# Power.net
KiCad netlist of a schematic drawn in Altium Designer
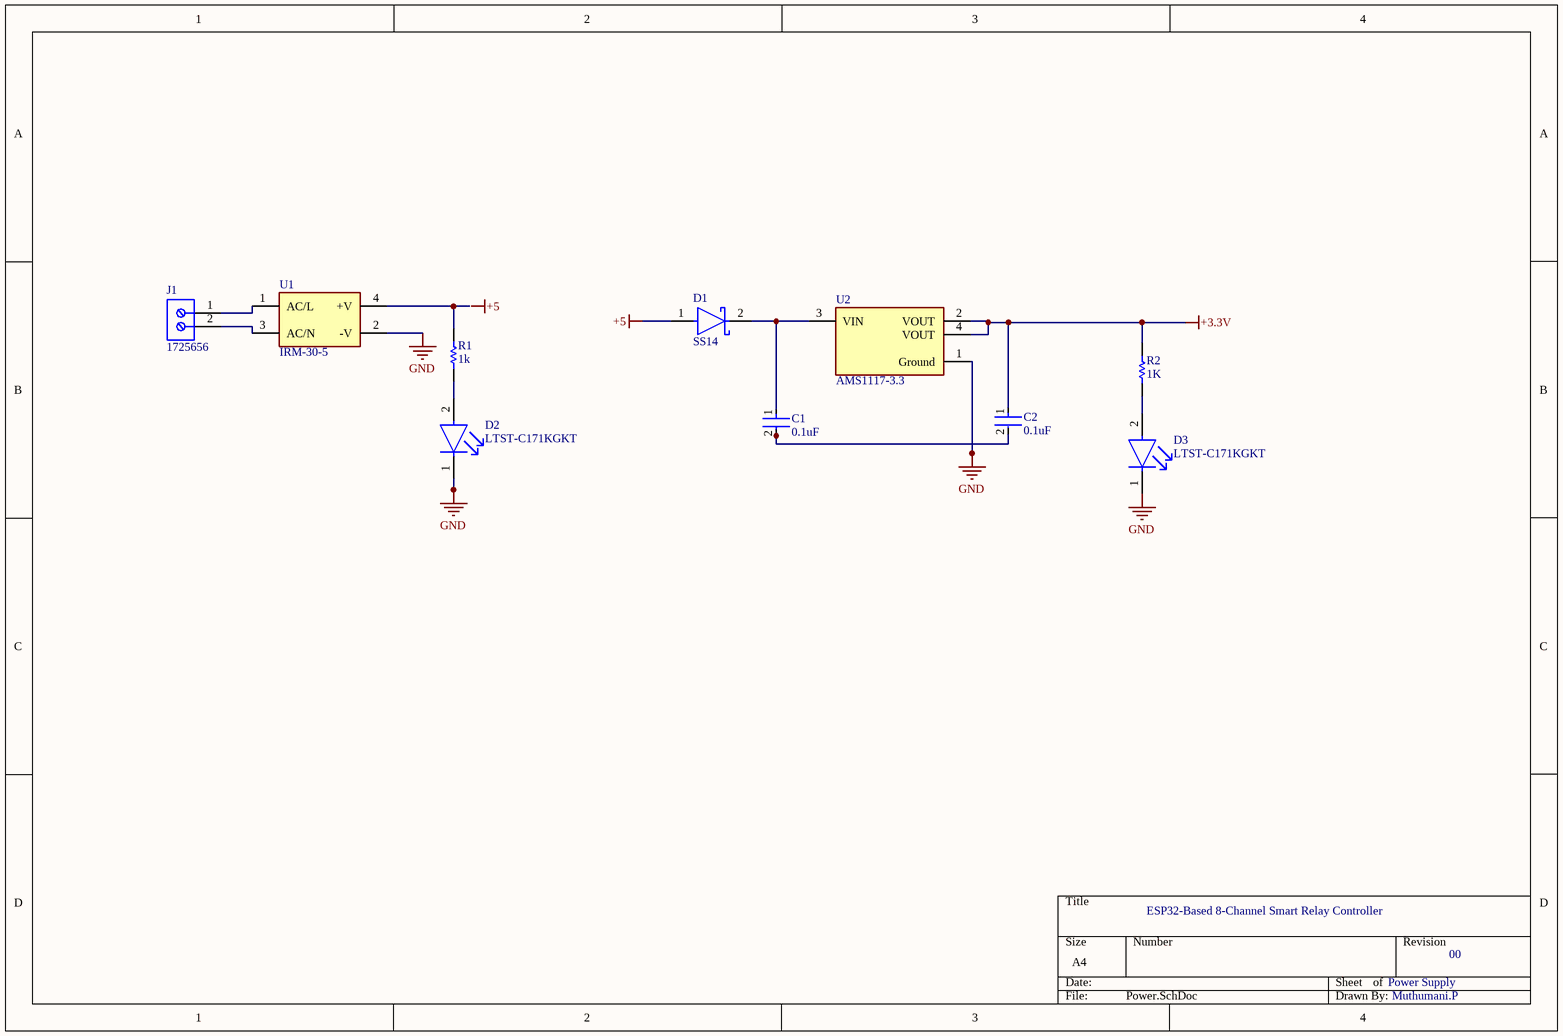
[diagram p0: Power.SchDoc]

(export (version "E")
  (design (tool "Eeschema 10.0.6"))
  (components
    (comp (ref "C1")
      (value "0.1uF")
      (footprint "FP-1206-L_3_2_0_2-W_1_6_0-MFG")
      (description "General Purpose Ceramic Capacitor, 1206, 2.2uF, 20%, X7R, 15%, 100V")
      (fields (field (name "TOLERANCE") "20%"))
      (libsource (lib "Altium Content Vault") (part "b4654b650e69147ec39a6b967a45e02"))
    )
    (comp (ref "C2")
      (value "0.1uF")
      (footprint "FP-1206-L_3_2_0_2-W_1_6_0-MFG")
      (description "General Purpose Ceramic Capacitor, 1206, 2.2uF, 20%, X7R, 15%, 100V")
      (fields (field (name "TOLERANCE") "20%"))
      (libsource (lib "Altium Content Vault") (part "b4654b650e69147ec39a6b967a45e02"))
    )
    (comp (ref "D1")
      (value "SS14")
      (footprint "FP-403AE-MFG")
      (description "DIODE SCHOTTKY 40V 1A SMA")
      (fields
        (field (name "MANUFACTURER") "ON Semiconductor")
        (field (name "OCTOPART") "https://octopart.com/ss14-on+semiconductor-29205033")
      )
      (libsource (lib "Altium Content Vault") (part "360ad2f4ac25a952324d13796385471"))
    )
    (comp (ref "D2")
      (value "LTST-C171KGKT")
      (footprint "FP-LTST-C171KGKT-MFG")
      (description "LED GREEN CLEAR SMD")
      (libsource (lib "Altium Content Vault") (part "8706943c75ba83719d021d2fdc84c58"))
    )
    (comp (ref "D3")
      (value "LTST-C171KGKT")
      (footprint "FP-LTST-C171KGKT-MFG")
      (description "LED GREEN CLEAR SMD")
      (libsource (lib "Altium Content Vault") (part "8706943c75ba83719d021d2fdc84c58"))
    )
    (comp (ref "J1")
      (value "1725656")
      (footprint "PHOE-1725656-2")
      (description "Male Header, Pitch 2.54 mm, 1 x 2 Position, Height 9 mm, Tail Length 3.5 mm")
      (fields (field (name "MANUFACTURER") "Phoenix Contact"))
      (libsource (lib "Altium Content Vault") (part "CN-1P-F-TB2"))
    )
    (comp (ref "R1")
      (value "1k")
      (footprint "RESC2013X60X35ML10T20")
      (description "Chip Resistor, 1 KOhm, +/- 1%, 125 mW, -55 to 155 degC, 0805 (2012 Metric), RoHS, Tape and Reel")
      (fields (field (name "TOLERANCE") "1%") (field (name "MANUFACTURER") "Yageo"))
      (libsource (lib "Altium Content Vault") (part "RES-2"))
    )
    (comp (ref "R2")
      (value "1K")
      (footprint "RESC2013X60X35ML10T20")
      (description "Chip Resistor, 1 KOhm, +/- 1%, 125 mW, -55 to 155 degC, 0805 (2012 Metric), RoHS, Tape and Reel")
      (fields (field (name "TOLERANCE") "1%") (field (name "MANUFACTURER") "Yageo"))
      (libsource (lib "Altium Content Vault") (part "RES-2"))
    )
    (comp (ref "U1")
      (value "IRM-30-5")
      (footprint "FP-IRM-30-5-MFG")
      (description "AC/DC CONVERTER 5V 30W")
      (fields
        (field (name "OCTOPART") "https://octopart.com/irm-30-5-mean+well-50976023")
        (field (name "MANUFACTURER") "Mean Well")
      )
      (libsource (lib "Altium Content Vault") (part "dd3edbd1b454dd46fb0d728e1f65b64"))
    )
    (comp (ref "U2")
      (value "AMS1117-3.3")
      (footprint "FP-AMS1117-IPC_C")
      (description "LDO Voltage Regulators 1A, 3.3V")
      (fields
        (field (name "OCTOPART") "https://octopart.com/ams1117-3.3-advanced+monolithic+systems-25899300")
        (field (name "MANUFACTURER") "Advanced Monolithic Systems")
      )
      (libsource (lib "Altium Content Vault") (part "8bdbb5f8e77002000e30dd2845d0354"))
    )
  )
  (nets
    (net (code "1") (name "+3.3V") (class "Default")
      (node (ref "C2") (pin "1") (pinfunction "1_1") (pintype "passive"))
      (node (ref "R2") (pin "2") (pinfunction "2_2") (pintype "passive"))
      (node (ref "U2") (pin "2") (pinfunction "VOUT_2") (pintype "passive"))
      (node (ref "U2") (pin "4") (pinfunction "VOUT_4") (pintype "passive"))
    )
    (net (code "2") (name "+5") (class "Default")
      (node (ref "D1") (pin "1") (pinfunction "A_1") (pintype "passive"))
    )
    (net (code "3") (name "GND") (class "Default")
      (node (ref "D2") (pin "1") (pinfunction "C_1") (pintype "passive"))
      (node (ref "D3") (pin "1") (pinfunction "C_1") (pintype "passive"))
      (node (ref "U1") (pin "2") (pinfunction "-V_2") (pintype "power_in"))
      (node (ref "U2") (pin "1") (pinfunction "Ground_1") (pintype "power_in"))
    )
    (net (code "4") (name "Net-(C1-Pad2)") (class "Default")
      (node (ref "C1") (pin "2") (pinfunction "2_2") (pintype "passive"))
      (node (ref "C2") (pin "2") (pinfunction "2_2") (pintype "passive"))
    )
    (net (code "5") (name "Net-(D1-C)") (class "Default")
      (node (ref "C1") (pin "1") (pinfunction "1_1") (pintype "passive"))
      (node (ref "D1") (pin "2") (pinfunction "C_2") (pintype "passive"))
      (node (ref "U2") (pin "3") (pinfunction "VIN_3") (pintype "power_in"))
    )
    (net (code "6") (name "Net-(D2-A)") (class "Default")
      (node (ref "D2") (pin "2") (pinfunction "A_2") (pintype "passive"))
      (node (ref "R1") (pin "1") (pinfunction "1_1") (pintype "passive"))
    )
    (net (code "7") (name "Net-(D3-A)") (class "Default")
      (node (ref "D3") (pin "2") (pinfunction "A_2") (pintype "passive"))
      (node (ref "R2") (pin "1") (pinfunction "1_1") (pintype "passive"))
    )
    (net (code "8") (name "Net-(U1-+V)") (class "Default")
      (node (ref "R1") (pin "2") (pinfunction "2_2") (pintype "passive"))
      (node (ref "U1") (pin "4") (pinfunction "+V_4") (pintype "power_in"))
    )
    (net (code "9") (name "Net-(U1-AC{slash}L)") (class "Default")
      (node (ref "J1") (pin "1") (pinfunction "1_1") (pintype "passive"))
      (node (ref "U1") (pin "1") (pinfunction "AC/L_1") (pintype "power_in"))
    )
    (net (code "10") (name "Net-(U1-AC{slash}N)") (class "Default")
      (node (ref "J1") (pin "2") (pinfunction "2_2") (pintype "passive"))
      (node (ref "U1") (pin "3") (pinfunction "AC/N_3") (pintype "power_in"))
    )
  )
)
